# Digital_Inputs.net
KiCad netlist of a schematic drawn in Altium Designer
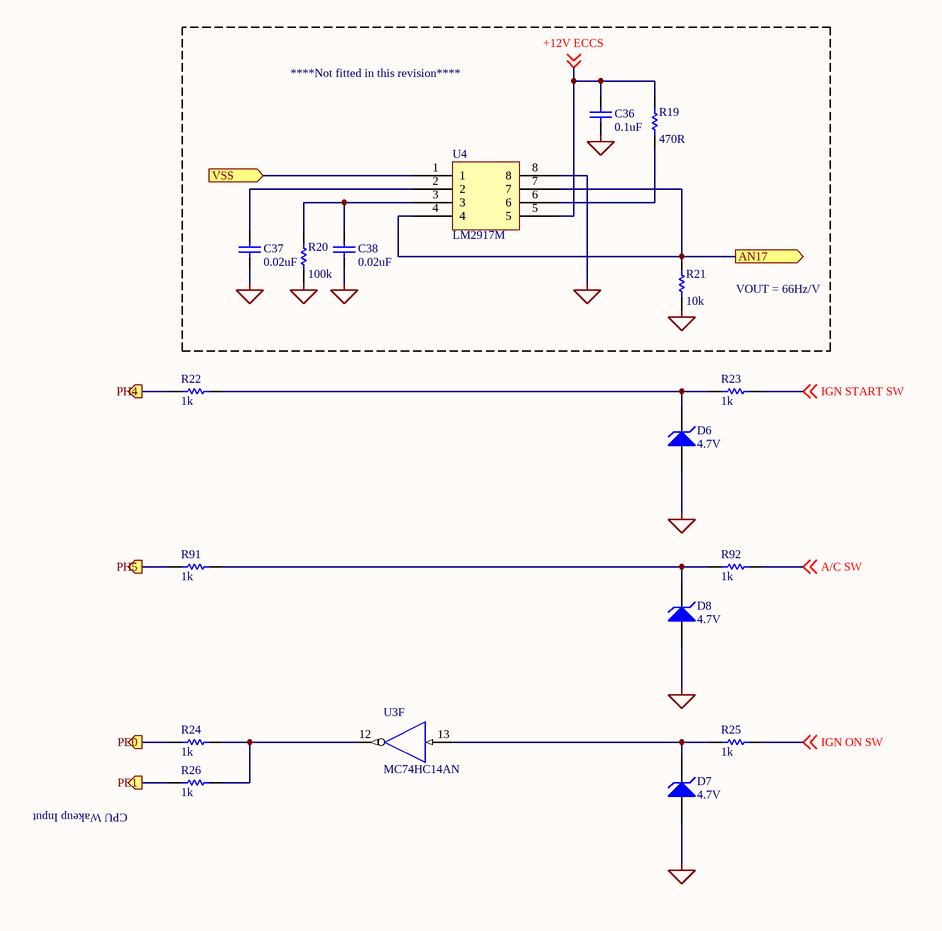
[diagram p0: Digital Inputs.SchDoc]

(export (version "E")
  (design (tool "Eeschema 10.0.6"))
  (components
    (comp (ref "C36")
      (value "0.1uF")
      (footprint "RAD-0.3")
      (description "Capacitor")
      (fields (field (name "PUBLISHER") "Altium Limited"))
      (libsource (lib "Miscellaneous Devices") (part "Cap"))
    )
    (comp (ref "C37")
      (value "0.02uF")
      (footprint "RAD-0.3")
      (description "Capacitor")
      (fields (field (name "PUBLISHER") "Altium Limited"))
      (libsource (lib "Miscellaneous Devices") (part "Cap"))
    )
    (comp (ref "C38")
      (value "0.02uF")
      (footprint "RAD-0.3")
      (description "Capacitor")
      (fields (field (name "PUBLISHER") "Altium Limited"))
      (libsource (lib "Miscellaneous Devices") (part "Cap"))
    )
    (comp (ref "D6")
      (value "4.7V")
      (footprint "DIODE-0.7")
      (description "Zener Diode")
      (fields (field (name "PUBLISHER") "Altium Limited"))
      (libsource (lib "Miscellaneous Devices") (part "D Zener"))
    )
    (comp (ref "D7")
      (value "4.7V")
      (footprint "DIODE-0.7")
      (description "Zener Diode")
      (fields (field (name "PUBLISHER") "Altium Limited"))
      (libsource (lib "Miscellaneous Devices") (part "D Zener"))
    )
    (comp (ref "D8")
      (value "4.7V")
      (footprint "DIODE-0.7")
      (description "Zener Diode")
      (fields (field (name "PUBLISHER") "Altium Limited"))
      (libsource (lib "Miscellaneous Devices") (part "D Zener"))
    )
    (comp (ref "R19")
      (value "470R")
      (footprint "AXIAL-0.3")
      (description "Resistor")
      (fields (field (name "PUBLISHER") "Altium Limited"))
      (libsource (lib "Miscellaneous Devices") (part "Res1"))
    )
    (comp (ref "R20")
      (value "100k")
      (footprint "AXIAL-0.3")
      (description "Resistor")
      (fields (field (name "PUBLISHER") "Altium Limited"))
      (libsource (lib "Miscellaneous Devices") (part "Res1"))
    )
    (comp (ref "R21")
      (value "10k")
      (footprint "AXIAL-0.3")
      (description "Resistor")
      (fields (field (name "PUBLISHER") "Altium Limited"))
      (libsource (lib "Miscellaneous Devices") (part "Res1"))
    )
    (comp (ref "R22")
      (value "1k")
      (footprint "AXIAL-0.3")
      (description "Resistor")
      (fields (field (name "PUBLISHER") "Altium Limited"))
      (libsource (lib "Miscellaneous Devices") (part "Res1"))
    )
    (comp (ref "R23")
      (value "1k")
      (footprint "AXIAL-0.3")
      (description "Resistor")
      (fields (field (name "PUBLISHER") "Altium Limited"))
      (libsource (lib "Miscellaneous Devices") (part "Res1"))
    )
    (comp (ref "R24")
      (value "1k")
      (footprint "AXIAL-0.3")
      (description "Resistor")
      (fields (field (name "PUBLISHER") "Altium Limited"))
      (libsource (lib "Miscellaneous Devices") (part "Res1"))
    )
    (comp (ref "R25")
      (value "1k")
      (footprint "AXIAL-0.3")
      (description "Resistor")
      (fields (field (name "PUBLISHER") "Altium Limited"))
      (libsource (lib "Miscellaneous Devices") (part "Res1"))
    )
    (comp (ref "R26")
      (value "1k")
      (footprint "AXIAL-0.3")
      (description "Resistor")
      (fields (field (name "PUBLISHER") "Altium Limited"))
      (libsource (lib "Miscellaneous Devices") (part "Res1"))
    )
    (comp (ref "R91")
      (value "1k")
      (footprint "AXIAL-0.3")
      (description "Resistor")
      (fields (field (name "PUBLISHER") "Altium Limited"))
      (libsource (lib "Miscellaneous Devices") (part "Res1"))
    )
    (comp (ref "R92")
      (value "1k")
      (footprint "AXIAL-0.3")
      (description "Resistor")
      (fields (field (name "PUBLISHER") "Altium Limited"))
      (libsource (lib "Miscellaneous Devices") (part "Res1"))
    )
    (comp (ref "U3")
      (value "MC74HC14AN")
      (footprint "646-06")
      (description "Hex Schmitt Trigger Inverter")
      (fields (field (name "PUBLISHER") "Altium Limited"))
      (libsource (lib "Motorola Logic Gate") (part "MC74HC14AN"))
    )
    (comp (ref "U4")
      (value "LM2917M")
      (footprint "SOIC8N_N")
      (libsource (lib "FreeEMS Schematic Library") (part "LM2917M"))
    )
  )
  (nets
    (net (code "1") (name "+12V ECCS") (class "Default")
      (node (ref "C36") (pin "2") (pinfunction "2_2") (pintype "passive"))
      (node (ref "R19") (pin "2") (pinfunction "2_2") (pintype "passive"))
      (node (ref "U4") (pin "5") (pinfunction "5_5") (pintype "passive"))
    )
    (net (code "2") (name "/AN17") (class "Default")
      (node (ref "R21") (pin "2") (pinfunction "2_2") (pintype "passive"))
      (node (ref "U4") (pin "4") (pinfunction "4_4") (pintype "passive"))
      (node (ref "U4") (pin "7") (pinfunction "7_7") (pintype "passive"))
    )
    (net (code "3") (name "/PE0") (class "Default")
      (node (ref "R24") (pin "2") (pinfunction "2_2") (pintype "passive"))
    )
    (net (code "4") (name "/PE1") (class "Default")
      (node (ref "R26") (pin "2") (pinfunction "2_2") (pintype "passive"))
    )
    (net (code "5") (name "/PH4") (class "Default")
      (node (ref "R22") (pin "2") (pinfunction "2_2") (pintype "passive"))
    )
    (net (code "6") (name "/PH5") (class "Default")
      (node (ref "R91") (pin "2") (pinfunction "2_2") (pintype "passive"))
    )
    (net (code "7") (name "/VSS") (class "Default")
      (node (ref "U4") (pin "1") (pinfunction "1_1") (pintype "passive"))
    )
    (net (code "8") (name "<NO NET>") (class "Default")
      (node (ref "C36") (pin "1") (pinfunction "1_1") (pintype "passive"))
      (node (ref "C37") (pin "1") (pinfunction "1_1") (pintype "passive"))
      (node (ref "C38") (pin "1") (pinfunction "1_1") (pintype "passive"))
      (node (ref "D6") (pin "1") (pinfunction "A_1") (pintype "passive"))
      (node (ref "D7") (pin "1") (pinfunction "A_1") (pintype "passive"))
      (node (ref "D8") (pin "1") (pinfunction "A_1") (pintype "passive"))
      (node (ref "R20") (pin "1") (pinfunction "1_1") (pintype "passive"))
      (node (ref "R21") (pin "1") (pinfunction "1_1") (pintype "passive"))
      (node (ref "U4") (pin "8") (pinfunction "8_8") (pintype "passive"))
    )
    (net (code "9") (name "A{slash}C SW") (class "Default")
      (node (ref "R92") (pin "2") (pinfunction "2_2") (pintype "passive"))
    )
    (net (code "10") (name "GND") (class "Default")
      (node (ref "U3") (pin "7") (pinfunction "GND_7") (pintype "power_in"))
    )
    (net (code "11") (name "IGN ON SW") (class "Default")
      (node (ref "R25") (pin "2") (pinfunction "2_2") (pintype "passive"))
    )
    (net (code "12") (name "IGN START SW") (class "Default")
      (node (ref "R23") (pin "2") (pinfunction "2_2") (pintype "passive"))
    )
    (net (code "13") (name "Net-(C37-Pad2)") (class "Default")
      (node (ref "C37") (pin "2") (pinfunction "2_2") (pintype "passive"))
      (node (ref "U4") (pin "2") (pinfunction "2_2") (pintype "passive"))
    )
    (net (code "14") (name "Net-(C38-Pad2)") (class "Default")
      (node (ref "C38") (pin "2") (pinfunction "2_2") (pintype "passive"))
      (node (ref "R20") (pin "2") (pinfunction "2_2") (pintype "passive"))
      (node (ref "U4") (pin "3") (pinfunction "3_3") (pintype "passive"))
    )
    (net (code "15") (name "Net-(D6-K)") (class "Default")
      (node (ref "D6") (pin "2") (pinfunction "K_2") (pintype "passive"))
      (node (ref "R22") (pin "1") (pinfunction "1_1") (pintype "passive"))
      (node (ref "R23") (pin "1") (pinfunction "1_1") (pintype "passive"))
    )
    (net (code "16") (name "Net-(D7-K)") (class "Default")
      (node (ref "D7") (pin "2") (pinfunction "K_2") (pintype "passive"))
      (node (ref "R25") (pin "1") (pinfunction "1_1") (pintype "passive"))
      (node (ref "U3") (pin "13") (pinfunction "A_13") (pintype "input"))
    )
    (net (code "17") (name "Net-(D8-K)") (class "Default")
      (node (ref "D8") (pin "2") (pinfunction "K_2") (pintype "passive"))
      (node (ref "R91") (pin "1") (pinfunction "1_1") (pintype "passive"))
      (node (ref "R92") (pin "1") (pinfunction "1_1") (pintype "passive"))
    )
    (net (code "18") (name "Net-(R19-Pad1)") (class "Default")
      (node (ref "R19") (pin "1") (pinfunction "1_1") (pintype "passive"))
      (node (ref "U4") (pin "6") (pinfunction "6_6") (pintype "passive"))
    )
    (net (code "19") (name "Net-(U3F-Y)") (class "Default")
      (node (ref "R24") (pin "1") (pinfunction "1_1") (pintype "passive"))
      (node (ref "R26") (pin "1") (pinfunction "1_1") (pintype "passive"))
      (node (ref "U3") (pin "12") (pinfunction "Y_12") (pintype "output"))
    )
    (net (code "20") (name "VDD") (class "Default")
      (node (ref "U3") (pin "14") (pinfunction "VDD_14") (pintype "power_in"))
    )
  )
)
